# Part05_DDR2.net
KiCad netlist of a schematic drawn in Altium Designer
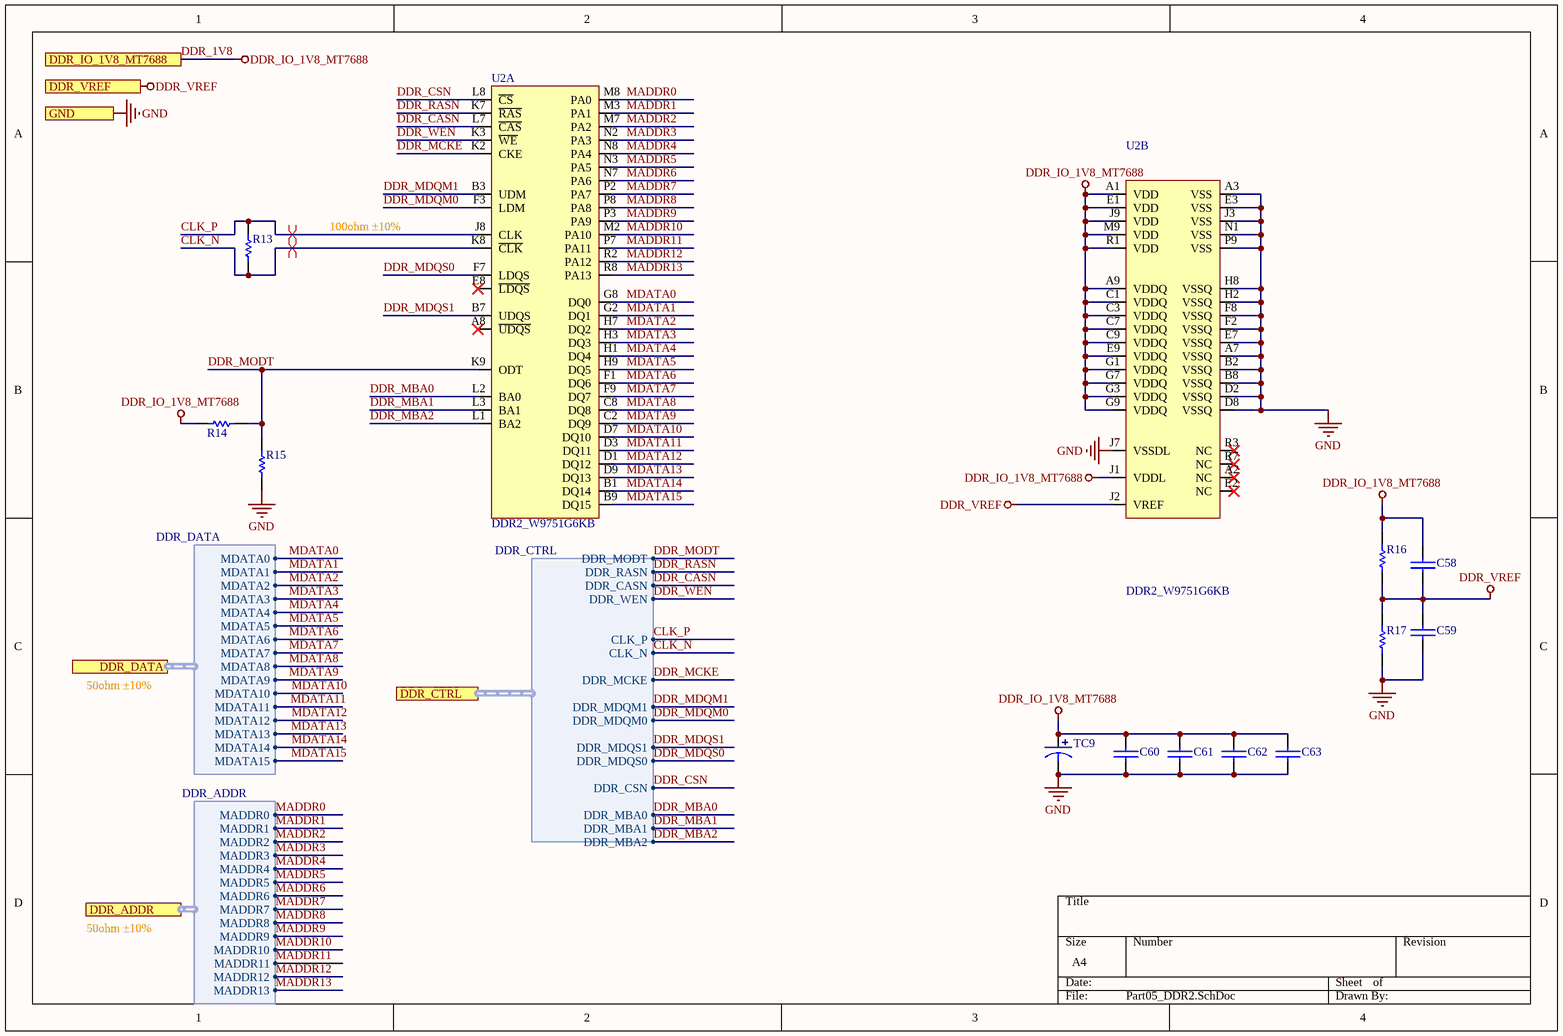
[diagram p0: Part05_DDR2.SchDoc]

(export (version "E")
  (design (tool "Eeschema 10.0.6"))
  (components
    (comp (ref "C58")
      (value "0.1uF/16V")
      (footprint "0402C")
      (description "无极性电容")
      (libsource (lib "电容") (part "CAP"))
    )
    (comp (ref "C59")
      (value "0.1uF/16V")
      (footprint "0402C")
      (description "无极性电容")
      (libsource (lib "电容") (part "CAP"))
    )
    (comp (ref "C60")
      (value "0.1uF/16V")
      (footprint "0402C")
      (description "无极性电容")
      (libsource (lib "电容") (part "CAP"))
    )
    (comp (ref "C61")
      (value "0.1uF/16V")
      (footprint "0402C")
      (description "无极性电容")
      (libsource (lib "电容") (part "CAP"))
    )
    (comp (ref "C62")
      (value "0.1uF/16V")
      (footprint "0402C")
      (description "无极性电容")
      (libsource (lib "电容") (part "CAP"))
    )
    (comp (ref "C63")
      (value "0.1uF/16V")
      (footprint "0402C")
      (description "无极性电容")
      (libsource (lib "电容") (part "CAP"))
    )
    (comp (ref "R13") (value "RES") (footprint "0402R") (libsource (lib "电阻") (part "RES")))
    (comp (ref "R14") (value "RES") (footprint "0402R") (libsource (lib "电阻") (part "RES")))
    (comp (ref "R15") (value "RES") (footprint "0402R") (libsource (lib "电阻") (part "RES")))
    (comp (ref "R16") (value "RES") (footprint "0402R") (libsource (lib "电阻") (part "RES")))
    (comp (ref "R17") (value "RES") (footprint "0402R") (libsource (lib "电阻") (part "RES")))
    (comp (ref "TC9")
      (value "4.7uF/6.3V")
      (footprint "TAJ-A/3216")
      (description "钽电容")
      (libsource (lib "电容") (part "TCAP"))
    )
    (comp (ref "U2")
      (value "DDR2_W9751G6KB")
      (footprint "MICT-RT-84")
      (libsource (lib "MT7688_Lib") (part "DDR2_W9751G6KB"))
    )
  )
  (nets
    (net (code "4") (name "/CLK_N") (class "Default")
      (node (ref "R13") (pin "2") (pinfunction "2_2") (pintype "passive"))
      (node (ref "U2") (pin "K8") (pinfunction "CLK_K8") (pintype "passive"))
    )
    (net (code "5") (name "/CLK_P") (class "Default")
      (node (ref "R13") (pin "1") (pinfunction "1_1") (pintype "passive"))
      (node (ref "U2") (pin "J8") (pinfunction "CLK_J8") (pintype "passive"))
    )
    (net (code "6") (name "/DDR_CASN") (class "Default")
      (node (ref "U2") (pin "L7") (pinfunction "~{CAS}_L7") (pintype "passive"))
    )
    (net (code "7") (name "/DDR_CSN") (class "Default")
      (node (ref "U2") (pin "L8") (pinfunction "~{CS}_L8") (pintype "passive"))
    )
    (net (code "8") (name "/DDR_MBA0") (class "Default")
      (node (ref "U2") (pin "L2") (pinfunction "BA0_L2") (pintype "passive"))
    )
    (net (code "9") (name "/DDR_MBA1") (class "Default")
      (node (ref "U2") (pin "L3") (pinfunction "BA1_L3") (pintype "passive"))
    )
    (net (code "10") (name "/DDR_MBA2") (class "Default")
      (node (ref "U2") (pin "L1") (pinfunction "BA2_L1") (pintype "passive"))
    )
    (net (code "11") (name "/DDR_MCKE") (class "Default")
      (node (ref "U2") (pin "K2") (pinfunction "CKE_K2") (pintype "passive"))
    )
    (net (code "12") (name "/DDR_MDQM0") (class "Default")
      (node (ref "U2") (pin "F3") (pinfunction "LDM_F3") (pintype "passive"))
    )
    (net (code "13") (name "/DDR_MDQM1") (class "Default")
      (node (ref "U2") (pin "B3") (pinfunction "UDM_B3") (pintype "passive"))
    )
    (net (code "14") (name "/DDR_MDQS0") (class "Default")
      (node (ref "U2") (pin "F7") (pinfunction "LDQS_F7") (pintype "passive"))
    )
    (net (code "15") (name "/DDR_MDQS1") (class "Default")
      (node (ref "U2") (pin "B7") (pinfunction "UDQS_B7") (pintype "passive"))
    )
    (net (code "16") (name "/DDR_MODT") (class "Default")
      (node (ref "R14") (pin "2") (pinfunction "2_2") (pintype "passive"))
      (node (ref "R15") (pin "1") (pinfunction "1_1") (pintype "passive"))
      (node (ref "U2") (pin "K9") (pinfunction "ODT_K9") (pintype "passive"))
    )
    (net (code "17") (name "/DDR_RASN") (class "Default")
      (node (ref "U2") (pin "K7") (pinfunction "~{RAS}_K7") (pintype "passive"))
    )
    (net (code "18") (name "/DDR_WEN") (class "Default")
      (node (ref "U2") (pin "K3") (pinfunction "WE_K3") (pintype "passive"))
    )
    (net (code "19") (name "/MADDR0") (class "Default")
      (node (ref "U2") (pin "M8") (pinfunction "PA0_M8") (pintype "passive"))
    )
    (net (code "20") (name "/MADDR1") (class "Default")
      (node (ref "U2") (pin "M3") (pinfunction "PA1_M3") (pintype "passive"))
    )
    (net (code "21") (name "/MADDR2") (class "Default")
      (node (ref "U2") (pin "M7") (pinfunction "PA2_M7") (pintype "passive"))
    )
    (net (code "22") (name "/MADDR3") (class "Default")
      (node (ref "U2") (pin "N2") (pinfunction "PA3_N2") (pintype "passive"))
    )
    (net (code "23") (name "/MADDR4") (class "Default")
      (node (ref "U2") (pin "N8") (pinfunction "PA4_N8") (pintype "passive"))
    )
    (net (code "24") (name "/MADDR5") (class "Default")
      (node (ref "U2") (pin "N3") (pinfunction "PA5_N3") (pintype "passive"))
    )
    (net (code "25") (name "/MADDR6") (class "Default")
      (node (ref "U2") (pin "N7") (pinfunction "PA6_N7") (pintype "passive"))
    )
    (net (code "26") (name "/MADDR7") (class "Default")
      (node (ref "U2") (pin "P2") (pinfunction "PA7_P2") (pintype "passive"))
    )
    (net (code "27") (name "/MADDR8") (class "Default")
      (node (ref "U2") (pin "P8") (pinfunction "PA8_P8") (pintype "passive"))
    )
    (net (code "28") (name "/MADDR9") (class "Default")
      (node (ref "U2") (pin "P3") (pinfunction "PA9_P3") (pintype "passive"))
    )
    (net (code "29") (name "/MADDR10") (class "Default")
      (node (ref "U2") (pin "M2") (pinfunction "PA10_M2") (pintype "passive"))
    )
    (net (code "30") (name "/MADDR11") (class "Default")
      (node (ref "U2") (pin "P7") (pinfunction "PA11_P7") (pintype "passive"))
    )
    (net (code "31") (name "/MADDR12") (class "Default")
      (node (ref "U2") (pin "R2") (pinfunction "PA12_R2") (pintype "passive"))
    )
    (net (code "32") (name "/MADDR13") (class "Default")
      (node (ref "U2") (pin "R8") (pinfunction "PA13_R8") (pintype "passive"))
    )
    (net (code "33") (name "/MDATA0") (class "Default")
      (node (ref "U2") (pin "G8") (pinfunction "DQ0_G8") (pintype "passive"))
    )
    (net (code "34") (name "/MDATA1") (class "Default")
      (node (ref "U2") (pin "G2") (pinfunction "DQ1_G2") (pintype "passive"))
    )
    (net (code "35") (name "/MDATA2") (class "Default")
      (node (ref "U2") (pin "H7") (pinfunction "DQ2_H7") (pintype "passive"))
    )
    (net (code "36") (name "/MDATA3") (class "Default")
      (node (ref "U2") (pin "H3") (pinfunction "DQ3_H3") (pintype "passive"))
    )
    (net (code "37") (name "/MDATA4") (class "Default")
      (node (ref "U2") (pin "H1") (pinfunction "DQ4_H1") (pintype "passive"))
    )
    (net (code "38") (name "/MDATA5") (class "Default")
      (node (ref "U2") (pin "H9") (pinfunction "DQ5_H9") (pintype "passive"))
    )
    (net (code "39") (name "/MDATA6") (class "Default")
      (node (ref "U2") (pin "F1") (pinfunction "DQ6_F1") (pintype "passive"))
    )
    (net (code "40") (name "/MDATA7") (class "Default")
      (node (ref "U2") (pin "F9") (pinfunction "DQ7_F9") (pintype "passive"))
    )
    (net (code "41") (name "/MDATA8") (class "Default")
      (node (ref "U2") (pin "C8") (pinfunction "DQ8_C8") (pintype "passive"))
    )
    (net (code "42") (name "/MDATA9") (class "Default")
      (node (ref "U2") (pin "C2") (pinfunction "DQ9_C2") (pintype "passive"))
    )
    (net (code "43") (name "/MDATA10") (class "Default")
      (node (ref "U2") (pin "D7") (pinfunction "DQ10_D7") (pintype "passive"))
    )
    (net (code "44") (name "/MDATA11") (class "Default")
      (node (ref "U2") (pin "D3") (pinfunction "DQ11_D3") (pintype "passive"))
    )
    (net (code "45") (name "/MDATA12") (class "Default")
      (node (ref "U2") (pin "D1") (pinfunction "DQ12_D1") (pintype "passive"))
    )
    (net (code "46") (name "/MDATA13") (class "Default")
      (node (ref "U2") (pin "D9") (pinfunction "DQ13_D9") (pintype "passive"))
    )
    (net (code "47") (name "/MDATA14") (class "Default")
      (node (ref "U2") (pin "B1") (pinfunction "DQ14_B1") (pintype "passive"))
    )
    (net (code "48") (name "/MDATA15") (class "Default")
      (node (ref "U2") (pin "B9") (pinfunction "DQ15_B9") (pintype "passive"))
    )
    (net (code "52") (name "DDR_IO_1V8_MT7688") (class "Default")
      (node (ref "C58") (pin "1") (pinfunction "1_1") (pintype "passive"))
      (node (ref "C60") (pin "1") (pinfunction "1_1") (pintype "passive"))
      (node (ref "C61") (pin "1") (pinfunction "1_1") (pintype "passive"))
      (node (ref "C62") (pin "1") (pinfunction "1_1") (pintype "passive"))
      (node (ref "C63") (pin "1") (pinfunction "1_1") (pintype "passive"))
      (node (ref "R14") (pin "1") (pinfunction "1_1") (pintype "passive"))
      (node (ref "R16") (pin "1") (pinfunction "1_1") (pintype "passive"))
      (node (ref "TC9") (pin "1") (pinfunction "1_1") (pintype "passive"))
      (node (ref "U2") (pin "A1") (pinfunction "VDD_A1") (pintype "passive"))
      (node (ref "U2") (pin "A9") (pinfunction "VDDQ_A9") (pintype "passive"))
      (node (ref "U2") (pin "C1") (pinfunction "VDDQ_C1") (pintype "passive"))
      (node (ref "U2") (pin "C3") (pinfunction "VDDQ_C3") (pintype "passive"))
      (node (ref "U2") (pin "C7") (pinfunction "VDDQ_C7") (pintype "passive"))
      (node (ref "U2") (pin "C9") (pinfunction "VDDQ_C9") (pintype "passive"))
      (node (ref "U2") (pin "E1") (pinfunction "VDD_E1") (pintype "passive"))
      (node (ref "U2") (pin "E9") (pinfunction "VDDQ_E9") (pintype "passive"))
      (node (ref "U2") (pin "G1") (pinfunction "VDDQ_G1") (pintype "passive"))
      (node (ref "U2") (pin "G3") (pinfunction "VDDQ_G3") (pintype "passive"))
      (node (ref "U2") (pin "G7") (pinfunction "VDDQ_G7") (pintype "passive"))
      (node (ref "U2") (pin "G9") (pinfunction "VDDQ_G9") (pintype "passive"))
      (node (ref "U2") (pin "J1") (pinfunction "VDDL_J1") (pintype "passive"))
      (node (ref "U2") (pin "J9") (pinfunction "VDD_J9") (pintype "passive"))
      (node (ref "U2") (pin "M9") (pinfunction "VDD_M9") (pintype "passive"))
      (node (ref "U2") (pin "R1") (pinfunction "VDD_R1") (pintype "passive"))
    )
    (net (code "53") (name "DDR_VREF") (class "Default")
      (node (ref "C58") (pin "2") (pinfunction "2_2") (pintype "passive"))
      (node (ref "C59") (pin "1") (pinfunction "1_1") (pintype "passive"))
      (node (ref "R16") (pin "2") (pinfunction "2_2") (pintype "passive"))
      (node (ref "R17") (pin "1") (pinfunction "1_1") (pintype "passive"))
      (node (ref "U2") (pin "J2") (pinfunction "VREF_J2") (pintype "passive"))
    )
    (net (code "54") (name "GND") (class "Default")
      (node (ref "C59") (pin "2") (pinfunction "2_2") (pintype "passive"))
      (node (ref "C60") (pin "2") (pinfunction "2_2") (pintype "passive"))
      (node (ref "C61") (pin "2") (pinfunction "2_2") (pintype "passive"))
      (node (ref "C62") (pin "2") (pinfunction "2_2") (pintype "passive"))
      (node (ref "C63") (pin "2") (pinfunction "2_2") (pintype "passive"))
      (node (ref "R15") (pin "2") (pinfunction "2_2") (pintype "passive"))
      (node (ref "R17") (pin "2") (pinfunction "2_2") (pintype "passive"))
      (node (ref "TC9") (pin "2") (pinfunction "2_2") (pintype "passive"))
      (node (ref "U2") (pin "A3") (pinfunction "VSS_A3") (pintype "passive"))
      (node (ref "U2") (pin "A7") (pinfunction "VSSQ_A7") (pintype "passive"))
      (node (ref "U2") (pin "B2") (pinfunction "VSSQ_B2") (pintype "passive"))
      (node (ref "U2") (pin "B8") (pinfunction "VSSQ_B8") (pintype "passive"))
      (node (ref "U2") (pin "D2") (pinfunction "VSSQ_D2") (pintype "passive"))
      (node (ref "U2") (pin "D8") (pinfunction "VSSQ_D8") (pintype "passive"))
      (node (ref "U2") (pin "E3") (pinfunction "VSS_E3") (pintype "passive"))
      (node (ref "U2") (pin "E7") (pinfunction "VSSQ_E7") (pintype "passive"))
      (node (ref "U2") (pin "F2") (pinfunction "VSSQ_F2") (pintype "passive"))
      (node (ref "U2") (pin "F8") (pinfunction "VSSQ_F8") (pintype "passive"))
      (node (ref "U2") (pin "H2") (pinfunction "VSSQ_H2") (pintype "passive"))
      (node (ref "U2") (pin "H8") (pinfunction "VSSQ_H8") (pintype "passive"))
      (node (ref "U2") (pin "J3") (pinfunction "VSS_J3") (pintype "passive"))
      (node (ref "U2") (pin "J7") (pinfunction "VSSDL_J7") (pintype "passive"))
      (node (ref "U2") (pin "N1") (pinfunction "VSS_N1") (pintype "passive"))
      (node (ref "U2") (pin "P9") (pinfunction "VSS_P9") (pintype "passive"))
    )
    (net (code "55") (name "unconnected-(U2A-~{LDQS}-PadE8)") (class "Default")
      (node (ref "U2") (pin "E8") (pinfunction "~{LDQS}_E8") (pintype "passive+no_connect"))
    )
    (net (code "56") (name "unconnected-(U2A-~{UDQS}-PadA8)") (class "Default")
      (node (ref "U2") (pin "A8") (pinfunction "~{UDQS}_A8") (pintype "passive+no_connect"))
    )
    (net (code "57") (name "unconnected-(U2B-NC-PadA2)") (class "Default")
      (node (ref "U2") (pin "A2") (pinfunction "NC_A2") (pintype "passive+no_connect"))
    )
    (net (code "58") (name "unconnected-(U2B-NC-PadE2)") (class "Default")
      (node (ref "U2") (pin "E2") (pinfunction "NC_E2") (pintype "passive+no_connect"))
    )
    (net (code "59") (name "unconnected-(U2B-NC-PadR3)") (class "Default")
      (node (ref "U2") (pin "R3") (pinfunction "NC_R3") (pintype "passive+no_connect"))
    )
    (net (code "60") (name "unconnected-(U2B-NC-PadR7)") (class "Default")
      (node (ref "U2") (pin "R7") (pinfunction "NC_R7") (pintype "passive+no_connect"))
    )
  )
)
